# sensor_board_v0_52.net
KiCad netlist of a schematic drawn in EAGLE
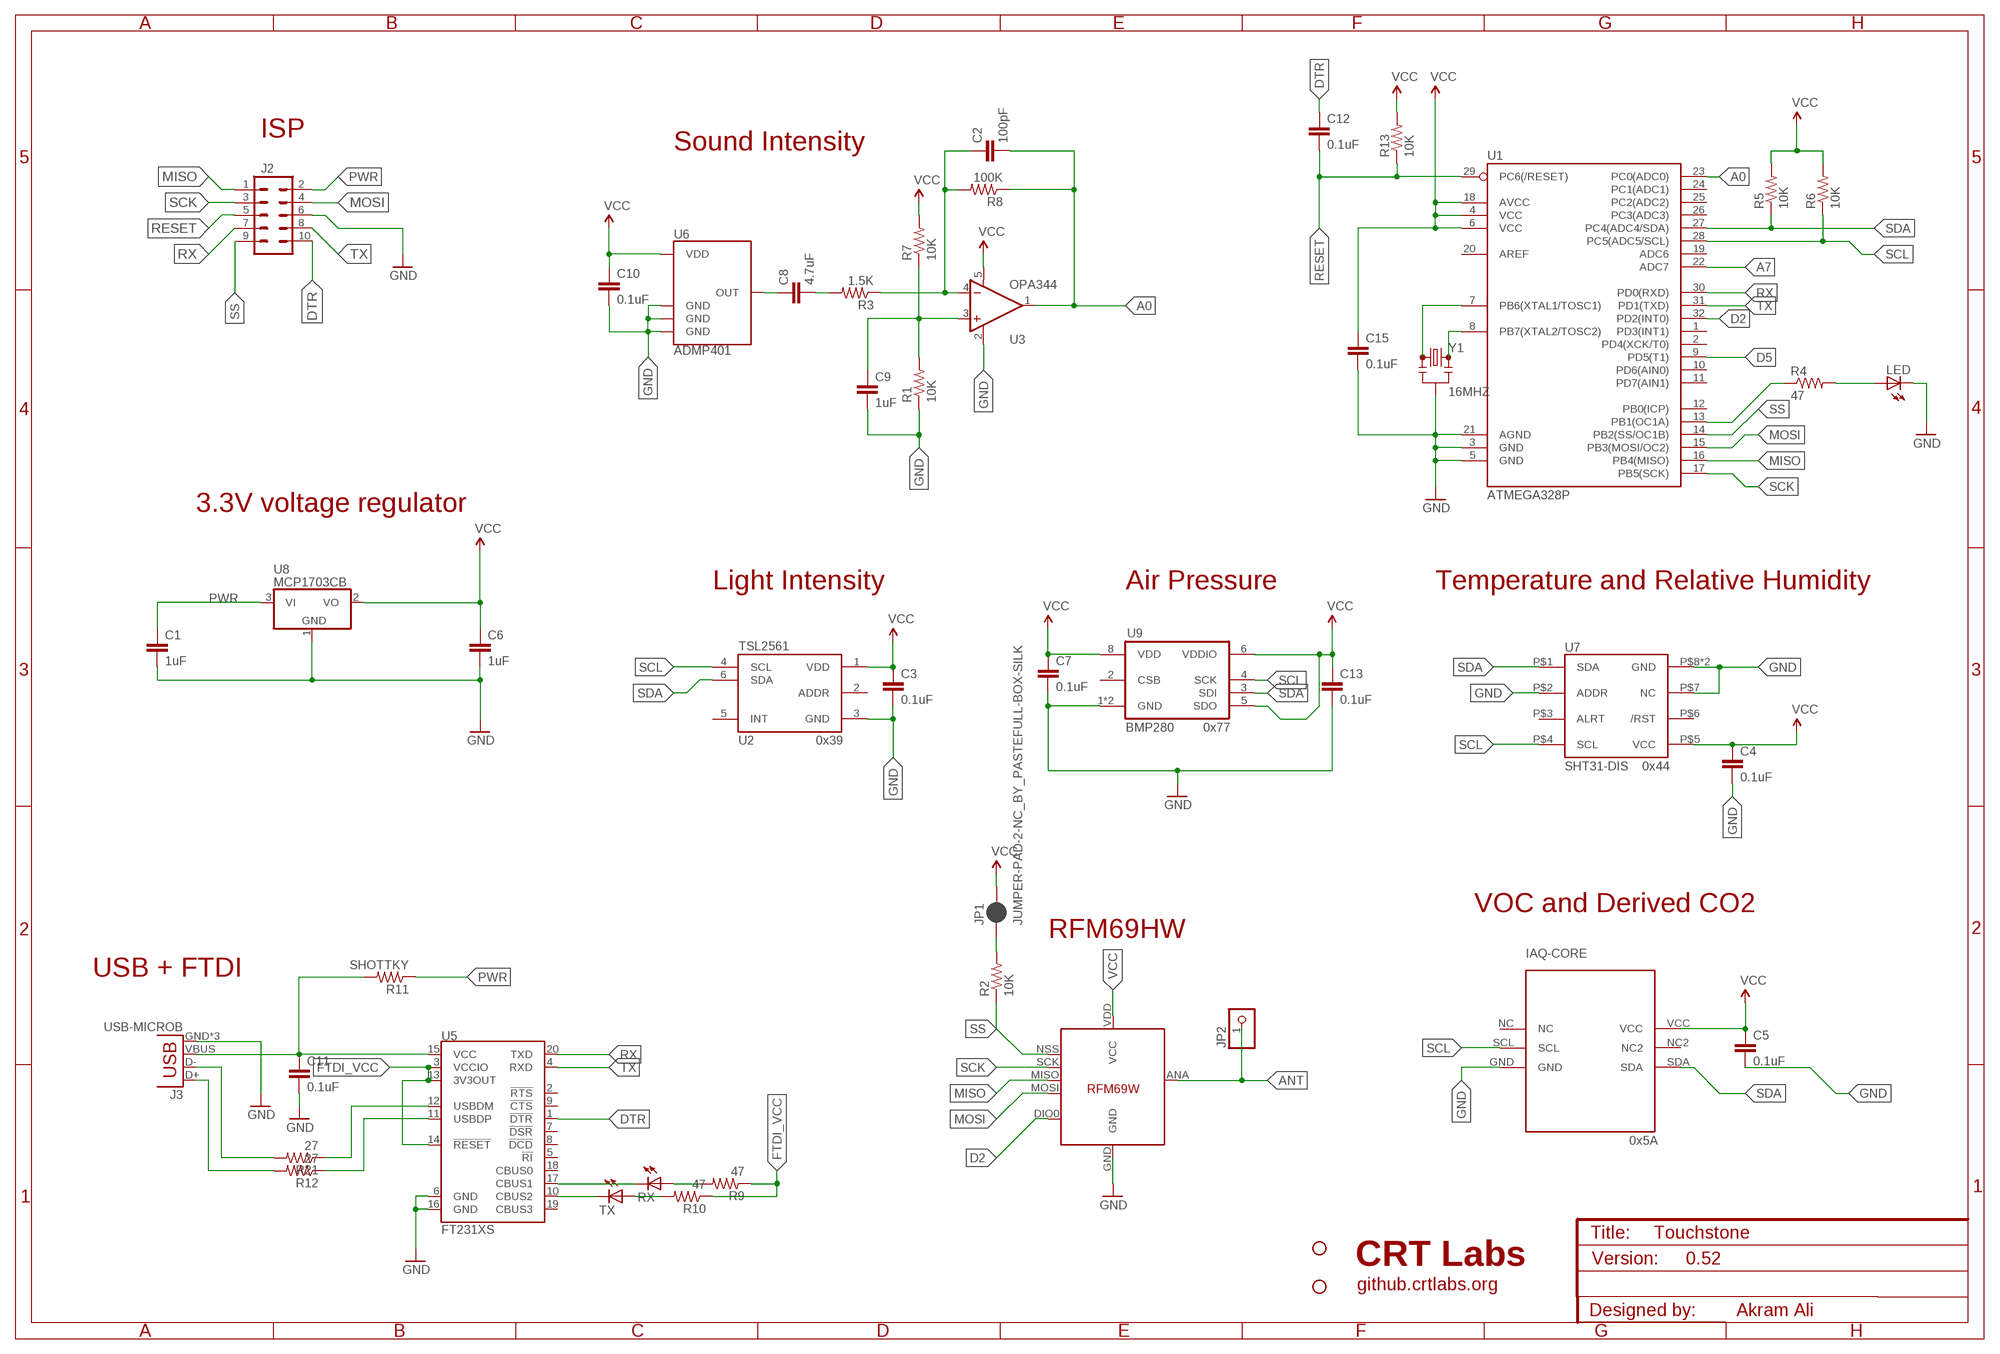
[diagram p0: schematic, sheet 1]

(export (version "E")
  (design (tool "Eeschema 10.0.6"))
  (components
    (comp (ref "C1")
      (value "1uF")
      (footprint "eagle-import:0805")
      (libsource (lib "eagle-import") (part "CAP0805"))
    )
    (comp (ref "C2")
      (value "100pF")
      (footprint "eagle-import:0805")
      (libsource (lib "eagle-import") (part "CAP0805"))
    )
    (comp (ref "C3")
      (value "0.1uF")
      (footprint "eagle-import:0805")
      (libsource (lib "eagle-import") (part "SparkFun-Passives_CAP0805"))
    )
    (comp (ref "C4")
      (value "0.1uF")
      (footprint "eagle-import:0805")
      (libsource (lib "eagle-import") (part "SparkFun-Passives_CAP0805"))
    )
    (comp (ref "C5")
      (value "0.1uF")
      (footprint "eagle-import:0805")
      (libsource (lib "eagle-import") (part "SparkFun-Passives_CAP0805"))
    )
    (comp (ref "C6")
      (value "1uF")
      (footprint "eagle-import:0805")
      (libsource (lib "eagle-import") (part "CAP0805"))
    )
    (comp (ref "C7")
      (value "0.1uF")
      (footprint "eagle-import:0805")
      (libsource (lib "eagle-import") (part "SparkFun-Passives_CAP0805"))
    )
    (comp (ref "C8")
      (value "4.7uF")
      (footprint "eagle-import:0805")
      (libsource (lib "eagle-import") (part "CAP0805"))
    )
    (comp (ref "C9")
      (value "1uF")
      (footprint "eagle-import:0805")
      (libsource (lib "eagle-import") (part "CAP0805"))
    )
    (comp (ref "C10")
      (value "0.1uF")
      (footprint "eagle-import:0805")
      (libsource (lib "eagle-import") (part "CAP0805"))
    )
    (comp (ref "C11")
      (value "0.1uF")
      (footprint "eagle-import:0805")
      (libsource (lib "eagle-import") (part "CAP0805"))
    )
    (comp (ref "C12")
      (value "0.1uF")
      (footprint "eagle-import:0805")
      (libsource (lib "eagle-import") (part "SparkFun-Passives_CAP0805"))
    )
    (comp (ref "C13")
      (value "0.1uF")
      (footprint "eagle-import:0805")
      (libsource (lib "eagle-import") (part "SparkFun-Passives_CAP0805"))
    )
    (comp (ref "C15")
      (value "0.1uF")
      (footprint "eagle-import:0805")
      (libsource (lib "eagle-import") (part "SparkFun-Passives_CAP0805"))
    )
    (comp (ref "H1")
      (value "STAND-OFF")
      (footprint "eagle-import:STAND-OFF")
      (libsource (lib "eagle-import") (part "STAND-OFF"))
    )
    (comp (ref "H2")
      (value "STAND-OFF")
      (footprint "eagle-import:STAND-OFF")
      (libsource (lib "eagle-import") (part "STAND-OFF"))
    )
    (comp (ref "IAQ-CORE")
      (value "IAQ-CORE")
      (footprint "eagle-import:IAQ-CORE")
      (fields (field (name "MPN") "IAQ CORE"))
      (libsource (lib "eagle-import") (part "IAQ-CORE"))
    )
    (comp (ref "J2")
      (value "M05X2PTH")
      (footprint "eagle-import:AVR_ICSP")
      (libsource (lib "eagle-import") (part "M05X2PTH"))
    )
    (comp (ref "J3")
      (value "USB-MICROB")
      (footprint "eagle-import:USB-MICROB")
      (libsource (lib "eagle-import") (part "USB-MICROB"))
    )
    (comp (ref "JP1")
      (value "JUMPER-PAD-2-NC_BY_PASTEFULL-BOX-SILK")
      (footprint "eagle-import:PAD-JUMPER-2-NC_BY_PASTE_YES_SILK_FULL_BOX")
      (libsource (lib "eagle-import") (part "JUMPER-PAD-2-NC_BY_PASTEFULL-BOX-SILK"))
    )
    (comp (ref "JP2")
      (value "PINHD-1X1")
      (footprint "eagle-import:1X01")
      (libsource (lib "eagle-import") (part "PINHD-1X1"))
    )
    (comp (ref "LED")
      (value "LEDCHIPLED_0805")
      (footprint "eagle-import:CHIPLED_0805")
      (libsource (lib "eagle-import") (part "LEDCHIPLED_0805"))
    )
    (comp (ref "R1")
      (value "10K")
      (footprint "eagle-import:0805")
      (libsource (lib "eagle-import") (part "RESISTOR0805-RES"))
    )
    (comp (ref "R2")
      (value "10K")
      (footprint "eagle-import:0805")
      (libsource (lib "eagle-import") (part "RESISTOR0805-RES"))
    )
    (comp (ref "R3")
      (value "1.5K")
      (footprint "eagle-import:0805")
      (libsource (lib "eagle-import") (part "RESISTOR0805-RES"))
    )
    (comp (ref "R4")
      (value "47")
      (footprint "eagle-import:0805")
      (libsource (lib "eagle-import") (part "SparkFun-Resistors_RESISTOR0805-RES"))
    )
    (comp (ref "R5")
      (value "10K")
      (footprint "eagle-import:0805")
      (libsource (lib "eagle-import") (part "SparkFun-Resistors_RESISTOR0805-RES"))
    )
    (comp (ref "R6")
      (value "10K")
      (footprint "eagle-import:0805")
      (libsource (lib "eagle-import") (part "SparkFun-Resistors_RESISTOR0805-RES"))
    )
    (comp (ref "R7")
      (value "10K")
      (footprint "eagle-import:0805")
      (libsource (lib "eagle-import") (part "RESISTOR0805-RES"))
    )
    (comp (ref "R8")
      (value "100K")
      (footprint "eagle-import:0805")
      (libsource (lib "eagle-import") (part "RESISTOR0805-RES"))
    )
    (comp (ref "R9")
      (value "47")
      (footprint "eagle-import:0805")
      (libsource (lib "eagle-import") (part "RESISTOR0805-RES"))
    )
    (comp (ref "R10")
      (value "47")
      (footprint "eagle-import:0805")
      (libsource (lib "eagle-import") (part "RESISTOR0805-RES"))
    )
    (comp (ref "R11")
      (value "SHOTTKY")
      (footprint "eagle-import:0805")
      (libsource (lib "eagle-import") (part "RESISTOR0805-RES"))
    )
    (comp (ref "R12")
      (value "27")
      (footprint "eagle-import:0805")
      (libsource (lib "eagle-import") (part "RESISTOR0805-RES"))
    )
    (comp (ref "R13")
      (value "10K")
      (footprint "eagle-import:0805")
      (libsource (lib "eagle-import") (part "RESISTOR0805-RES"))
    )
    (comp (ref "R21")
      (value "27")
      (footprint "eagle-import:0805")
      (libsource (lib "eagle-import") (part "RESISTOR0805-RES"))
    )
    (comp (ref "RX")
      (value "LEDCHIPLED_0805")
      (footprint "eagle-import:CHIPLED_0805")
      (libsource (lib "eagle-import") (part "LEDCHIPLED_0805"))
    )
    (comp (ref "TX")
      (value "LEDCHIPLED_0805")
      (footprint "eagle-import:CHIPLED_0805")
      (libsource (lib "eagle-import") (part "LEDCHIPLED_0805"))
    )
    (comp (ref "U1")
      (value "ATMEGA328P")
      (footprint "eagle-import:TQFP32-08")
      (fields (field (name "MPN") "ATMEGA328PB-AU"))
      (libsource (lib "eagle-import") (part "ATMEGA328P_TQFP"))
    )
    (comp (ref "U2")
      (value "TSL2561")
      (footprint "eagle-import:FN-6")
      (fields (field (name "MANF") "AMS-TAOS-USA-Inc.") (field (name "MPN") "TSL2561FN"))
      (libsource (lib "eagle-import") (part "TSL2561FN"))
    )
    (comp (ref "U3")
      (value "OPA344")
      (footprint "eagle-import:SOT23-5")
      (libsource (lib "eagle-import") (part "OPA344"))
    )
    (comp (ref "U4")
      (value "RFM69HW")
      (footprint "eagle-import:LOWPOWERLAB_RFM69W-MINPADS")
      (libsource (lib "eagle-import") (part "LOWPOWERLAB_RFM69"))
    )
    (comp (ref "U5")
      (value "FT231XS")
      (footprint "eagle-import:SSOP20_L")
      (libsource (lib "eagle-import") (part "FT231XS"))
    )
    (comp (ref "U6")
      (value "ADMP401")
      (footprint "eagle-import:ADMP401")
      (libsource (lib "eagle-import") (part "ADMP401"))
    )
    (comp (ref "U7")
      (value "SHT31-DIS")
      (footprint "eagle-import:SHT3X")
      (fields (field (name "MPN") "SHT31-DIS-B"))
      (libsource (lib "eagle-import") (part "SHT31-DIS"))
    )
    (comp (ref "U8")
      (value "MCP1703CB")
      (footprint "eagle-import:SOT23")
      (fields (field (name "MPN") "MCP1703T-2502E/CB"))
      (libsource (lib "eagle-import") (part "MCP1703CB"))
    )
    (comp (ref "U9")
      (value "BMP280")
      (footprint "eagle-import:BMP280")
      (libsource (lib "eagle-import") (part "BMP280"))
    )
    (comp (ref "Y1")
      (value "16MHZ")
      (footprint "eagle-import:RESONATOR-SMD")
      (libsource (lib "eagle-import") (part "RESONATOR16MHZ"))
    )
  )
  (nets
    (net (code "1") (name "A0") (class "Default")
      (node (ref "C2") (pin "2") (pinfunction "2_2") (pintype "passive"))
      (node (ref "R8") (pin "1") (pinfunction "1_1") (pintype "passive"))
      (node (ref "U1") (pin "23") (pinfunction "PC0(ADC0)_23") (pintype "bidirectional"))
      (node (ref "U3") (pin "1") (pinfunction "OUT_1") (pintype "output"))
    )
    (net (code "2") (name "A7") (class "Default")
      (node (ref "U1") (pin "22") (pinfunction "ADC7_22") (pintype "bidirectional"))
    )
    (net (code "3") (name "ANT") (class "Default")
      (node (ref "JP2") (pin "1") (pinfunction "1_1") (pintype "passive"))
      (node (ref "U4") (pin "ANA") (pinfunction "ANT_ANA") (pintype "passive"))
    )
    (net (code "4") (name "D2") (class "Default")
      (node (ref "U1") (pin "32") (pinfunction "PD2(INT0)_32") (pintype "bidirectional"))
      (node (ref "U4") (pin "DIO0") (pinfunction "DIO0_DIO0") (pintype "open_collector"))
    )
    (net (code "5") (name "D5") (class "Default")
      (node (ref "U1") (pin "9") (pinfunction "PD5(T1)_9") (pintype "bidirectional"))
    )
    (net (code "6") (name "DTR") (class "Default")
      (node (ref "C12") (pin "1") (pinfunction "1_1") (pintype "passive"))
      (node (ref "J2") (pin "10") (pinfunction "10_10") (pintype "passive"))
      (node (ref "U5") (pin "1") (pinfunction "~{DTR}_1") (pintype "bidirectional"))
    )
    (net (code "7") (name "FTDI_VCC") (class "Default")
      (node (ref "R10") (pin "1") (pinfunction "1_1") (pintype "passive"))
      (node (ref "R9") (pin "1") (pinfunction "1_1") (pintype "passive"))
      (node (ref "U5") (pin "13") (pinfunction "3V3OUT_13") (pintype "bidirectional"))
      (node (ref "U5") (pin "14") (pinfunction "~{RESET}_14") (pintype "bidirectional"))
      (node (ref "U5") (pin "3") (pinfunction "VCCIO_3") (pintype "bidirectional"))
    )
    (net (code "8") (name "GND") (class "Default")
      (node (ref "C1") (pin "2") (pinfunction "2_2") (pintype "passive"))
      (node (ref "C10") (pin "2") (pinfunction "2_2") (pintype "passive"))
      (node (ref "C11") (pin "2") (pinfunction "2_2") (pintype "passive"))
      (node (ref "C13") (pin "2") (pinfunction "2_2") (pintype "passive"))
      (node (ref "C15") (pin "2") (pinfunction "2_2") (pintype "passive"))
      (node (ref "C3") (pin "2") (pinfunction "2_2") (pintype "passive"))
      (node (ref "C4") (pin "2") (pinfunction "2_2") (pintype "passive"))
      (node (ref "C5") (pin "2") (pinfunction "2_2") (pintype "passive"))
      (node (ref "C6") (pin "2") (pinfunction "2_2") (pintype "passive"))
      (node (ref "C7") (pin "2") (pinfunction "2_2") (pintype "passive"))
      (node (ref "C9") (pin "2") (pinfunction "2_2") (pintype "passive"))
      (node (ref "IAQ-CORE") (pin "GND") (pinfunction "GND_GND") (pintype "bidirectional"))
      (node (ref "J2") (pin "6") (pinfunction "6_6") (pintype "passive"))
      (node (ref "J3") (pin "GND") (pinfunction "GND_GND") (pintype "bidirectional"))
      (node (ref "J3") (pin "MT1") (pinfunction "GND_MT1") (pintype "bidirectional"))
      (node (ref "J3") (pin "MT2") (pinfunction "GND_MT2") (pintype "bidirectional"))
      (node (ref "LED") (pin "C") (pinfunction "C_C") (pintype "passive"))
      (node (ref "R1") (pin "1") (pinfunction "1_1") (pintype "passive"))
      (node (ref "U1") (pin "21") (pinfunction "AGND_21") (pintype "bidirectional"))
      (node (ref "U1") (pin "3") (pinfunction "GND_3") (pintype "bidirectional"))
      (node (ref "U1") (pin "5") (pinfunction "GND_5") (pintype "bidirectional"))
      (node (ref "U2") (pin "3") (pinfunction "GND_3") (pintype "power_in"))
      (node (ref "U3") (pin "2") (pinfunction "V-_2") (pintype "power_in"))
      (node (ref "U4") (pin "GND") (pinfunction "GND_GND") (pintype "power_in"))
      (node (ref "U5") (pin "16") (pinfunction "GND_16") (pintype "bidirectional"))
      (node (ref "U5") (pin "6") (pinfunction "GND_6") (pintype "bidirectional"))
      (node (ref "U6") (pin "2") (pinfunction "GND_2") (pintype "bidirectional"))
      (node (ref "U6") (pin "4") (pinfunction "GND_4") (pintype "bidirectional"))
      (node (ref "U6") (pin "6") (pinfunction "GND_6") (pintype "bidirectional"))
      (node (ref "U7") (pin "P$2") (pinfunction "ADDR_P$2") (pintype "bidirectional"))
      (node (ref "U7") (pin "P$7") (pinfunction "NC_P$7") (pintype "bidirectional"))
      (node (ref "U7") (pin "P$8") (pinfunction "GND_P$8") (pintype "bidirectional"))
      (node (ref "U7") (pin "PAD") (pinfunction "GND_PAD") (pintype "bidirectional"))
      (node (ref "U8") (pin "1") (pinfunction "GND_1") (pintype "passive"))
      (node (ref "U9") (pin "1") (pinfunction "GND_1") (pintype "power_in"))
      (node (ref "U9") (pin "7") (pinfunction "GND_7") (pintype "power_in"))
      (node (ref "Y1") (pin "2") (pinfunction "2_2") (pintype "passive"))
    )
    (net (code "9") (name "MISO") (class "Default")
      (node (ref "J2") (pin "1") (pinfunction "1_1") (pintype "passive"))
      (node (ref "U1") (pin "16") (pinfunction "PB4(MISO)_16") (pintype "bidirectional"))
      (node (ref "U4") (pin "MISO") (pinfunction "MISO_MISO") (pintype "input"))
    )
    (net (code "10") (name "MOSI") (class "Default")
      (node (ref "J2") (pin "4") (pinfunction "4_4") (pintype "passive"))
      (node (ref "U1") (pin "15") (pinfunction "PB3(MOSI/OC2)_15") (pintype "bidirectional"))
      (node (ref "U4") (pin "MOSI") (pinfunction "MOSI_MOSI") (pintype "output"))
    )
    (net (code "11") (name "Net-(C8-Pad2)") (class "Default")
      (node (ref "C8") (pin "2") (pinfunction "2_2") (pintype "passive"))
      (node (ref "R3") (pin "2") (pinfunction "2_2") (pintype "passive"))
    )
    (net (code "12") (name "Net-(J3-PadD+)") (class "Default")
      (node (ref "J3") (pin "D+") (pinfunction "D+_D+") (pintype "bidirectional"))
      (node (ref "R12") (pin "2") (pinfunction "2_2") (pintype "passive"))
    )
    (net (code "13") (name "Net-(J3-PadD-)") (class "Default")
      (node (ref "J3") (pin "D-") (pinfunction "D-_D-") (pintype "bidirectional"))
      (node (ref "R21") (pin "2") (pinfunction "2_2") (pintype "passive"))
    )
    (net (code "14") (name "Net-(JP1-Pad1)") (class "Default")
      (node (ref "JP1") (pin "1") (pinfunction "1_1") (pintype "passive"))
      (node (ref "R2") (pin "2") (pinfunction "2_2") (pintype "passive"))
    )
    (net (code "15") (name "Net-(LED-PadA)") (class "Default")
      (node (ref "LED") (pin "A") (pinfunction "A_A") (pintype "passive"))
      (node (ref "R4") (pin "2") (pinfunction "2_2") (pintype "passive"))
    )
    (net (code "16") (name "Net-(R9-Pad2)") (class "Default")
      (node (ref "R9") (pin "2") (pinfunction "2_2") (pintype "passive"))
      (node (ref "RX") (pin "A") (pinfunction "A_A") (pintype "passive"))
    )
    (net (code "17") (name "Net-(R10-Pad2)") (class "Default")
      (node (ref "R10") (pin "2") (pinfunction "2_2") (pintype "passive"))
      (node (ref "TX") (pin "A") (pinfunction "A_A") (pintype "passive"))
    )
    (net (code "18") (name "Net-(U1-PB1(OC1A))") (class "Default")
      (node (ref "R4") (pin "1") (pinfunction "1_1") (pintype "passive"))
      (node (ref "U1") (pin "13") (pinfunction "PB1(OC1A)_13") (pintype "bidirectional"))
    )
    (net (code "19") (name "Net-(U1-PB6(XTAL1{slash}TOSC1))") (class "Default")
      (node (ref "U1") (pin "7") (pinfunction "PB6(XTAL1/TOSC1)_7") (pintype "bidirectional"))
      (node (ref "Y1") (pin "1") (pinfunction "1_1") (pintype "passive"))
    )
    (net (code "20") (name "Net-(U1-PB7(XTAL2{slash}TOSC2))") (class "Default")
      (node (ref "U1") (pin "8") (pinfunction "PB7(XTAL2/TOSC2)_8") (pintype "bidirectional"))
      (node (ref "Y1") (pin "3") (pinfunction "3_3") (pintype "passive"))
    )
    (net (code "21") (name "Net-(U3-+IN)") (class "Default")
      (node (ref "C9") (pin "1") (pinfunction "1_1") (pintype "passive"))
      (node (ref "R1") (pin "2") (pinfunction "2_2") (pintype "passive"))
      (node (ref "R7") (pin "1") (pinfunction "1_1") (pintype "passive"))
      (node (ref "U3") (pin "3") (pinfunction "+IN_3") (pintype "input"))
    )
    (net (code "22") (name "Net-(U3--IN)") (class "Default")
      (node (ref "C2") (pin "1") (pinfunction "1_1") (pintype "passive"))
      (node (ref "R3") (pin "1") (pinfunction "1_1") (pintype "passive"))
      (node (ref "R8") (pin "2") (pinfunction "2_2") (pintype "passive"))
      (node (ref "U3") (pin "4") (pinfunction "-IN_4") (pintype "input"))
    )
    (net (code "23") (name "Net-(U5-CBUS1)") (class "Default")
      (node (ref "RX") (pin "C") (pinfunction "C_C") (pintype "passive"))
      (node (ref "U5") (pin "17") (pinfunction "CBUS1_17") (pintype "bidirectional"))
    )
    (net (code "24") (name "Net-(U5-CBUS2)") (class "Default")
      (node (ref "TX") (pin "C") (pinfunction "C_C") (pintype "passive"))
      (node (ref "U5") (pin "10") (pinfunction "CBUS2_10") (pintype "bidirectional"))
    )
    (net (code "25") (name "Net-(U5-USBDM)") (class "Default")
      (node (ref "R21") (pin "1") (pinfunction "1_1") (pintype "passive"))
      (node (ref "U5") (pin "12") (pinfunction "USBDM_12") (pintype "bidirectional"))
    )
    (net (code "26") (name "Net-(U5-USBDP)") (class "Default")
      (node (ref "R12") (pin "1") (pinfunction "1_1") (pintype "passive"))
      (node (ref "U5") (pin "11") (pinfunction "USBDP_11") (pintype "bidirectional"))
    )
    (net (code "27") (name "Net-(U5-VCC)") (class "Default")
      (node (ref "C11") (pin "1") (pinfunction "1_1") (pintype "passive"))
      (node (ref "J3") (pin "VBUS") (pinfunction "VBUS_VBUS") (pintype "bidirectional"))
      (node (ref "R11") (pin "2") (pinfunction "2_2") (pintype "passive"))
      (node (ref "U5") (pin "15") (pinfunction "VCC_15") (pintype "bidirectional"))
    )
    (net (code "28") (name "Net-(U6-OUT)") (class "Default")
      (node (ref "C8") (pin "1") (pinfunction "1_1") (pintype "passive"))
      (node (ref "U6") (pin "1") (pinfunction "OUT_1") (pintype "bidirectional"))
    )
    (net (code "29") (name "PWR") (class "Default")
      (node (ref "C1") (pin "1") (pinfunction "1_1") (pintype "passive"))
      (node (ref "J2") (pin "2") (pinfunction "2_2") (pintype "passive"))
      (node (ref "R11") (pin "1") (pinfunction "1_1") (pintype "passive"))
      (node (ref "U8") (pin "3") (pinfunction "VI_3") (pintype "input"))
    )
    (net (code "30") (name "RESET") (class "Default")
      (node (ref "C12") (pin "2") (pinfunction "2_2") (pintype "passive"))
      (node (ref "J2") (pin "5") (pinfunction "5_5") (pintype "passive"))
      (node (ref "R13") (pin "1") (pinfunction "1_1") (pintype "passive"))
      (node (ref "U1") (pin "29") (pinfunction "PC6(/RESET)_29") (pintype "bidirectional"))
    )
    (net (code "31") (name "RX") (class "Default")
      (node (ref "J2") (pin "7") (pinfunction "7_7") (pintype "passive"))
      (node (ref "U1") (pin "30") (pinfunction "PD0(RXD)_30") (pintype "bidirectional"))
      (node (ref "U5") (pin "20") (pinfunction "TXD_20") (pintype "bidirectional"))
    )
    (net (code "32") (name "SCK") (class "Default")
      (node (ref "J2") (pin "3") (pinfunction "3_3") (pintype "passive"))
      (node (ref "U1") (pin "17") (pinfunction "PB5(SCK)_17") (pintype "bidirectional"))
      (node (ref "U4") (pin "SCK") (pinfunction "SCK_SCK") (pintype "input"))
    )
    (net (code "33") (name "SCL") (class "Default")
      (node (ref "IAQ-CORE") (pin "SCL") (pinfunction "SCL_SCL") (pintype "bidirectional"))
      (node (ref "R6") (pin "1") (pinfunction "1_1") (pintype "passive"))
      (node (ref "U1") (pin "28") (pinfunction "PC5(ADC5/SCL)_28") (pintype "bidirectional"))
      (node (ref "U2") (pin "4") (pinfunction "SCL_4") (pintype "input"))
      (node (ref "U7") (pin "P$4") (pinfunction "SCL_P$4") (pintype "bidirectional"))
      (node (ref "U9") (pin "4") (pinfunction "SCK_4") (pintype "bidirectional"))
    )
    (net (code "34") (name "SDA") (class "Default")
      (node (ref "IAQ-CORE") (pin "SDA") (pinfunction "SDA_SDA") (pintype "bidirectional"))
      (node (ref "R5") (pin "1") (pinfunction "1_1") (pintype "passive"))
      (node (ref "U1") (pin "27") (pinfunction "PC4(ADC4/SDA)_27") (pintype "bidirectional"))
      (node (ref "U2") (pin "6") (pinfunction "SDA_6") (pintype "bidirectional"))
      (node (ref "U7") (pin "P$1") (pinfunction "SDA_P$1") (pintype "bidirectional"))
      (node (ref "U9") (pin "3") (pinfunction "SDI_3") (pintype "bidirectional"))
    )
    (net (code "35") (name "SS") (class "Default")
      (node (ref "J2") (pin "9") (pinfunction "9_9") (pintype "passive"))
      (node (ref "R2") (pin "1") (pinfunction "1_1") (pintype "passive"))
      (node (ref "U1") (pin "14") (pinfunction "PB2(SS/OC1B)_14") (pintype "bidirectional"))
      (node (ref "U4") (pin "NSS") (pinfunction "SEL_NSS") (pintype "input"))
    )
    (net (code "36") (name "TX") (class "Default")
      (node (ref "J2") (pin "8") (pinfunction "8_8") (pintype "passive"))
      (node (ref "U1") (pin "31") (pinfunction "PD1(TXD)_31") (pintype "bidirectional"))
      (node (ref "U5") (pin "4") (pinfunction "RXD_4") (pintype "bidirectional"))
    )
    (net (code "37") (name "VCC") (class "Default")
      (node (ref "C10") (pin "1") (pinfunction "1_1") (pintype "passive"))
      (node (ref "C13") (pin "1") (pinfunction "1_1") (pintype "passive"))
      (node (ref "C15") (pin "1") (pinfunction "1_1") (pintype "passive"))
      (node (ref "C3") (pin "1") (pinfunction "1_1") (pintype "passive"))
      (node (ref "C4") (pin "1") (pinfunction "1_1") (pintype "passive"))
      (node (ref "C5") (pin "1") (pinfunction "1_1") (pintype "passive"))
      (node (ref "C6") (pin "1") (pinfunction "1_1") (pintype "passive"))
      (node (ref "C7") (pin "1") (pinfunction "1_1") (pintype "passive"))
      (node (ref "IAQ-CORE") (pin "VCC") (pinfunction "VCC_VCC") (pintype "bidirectional"))
      (node (ref "JP1") (pin "2") (pinfunction "2_2") (pintype "passive"))
      (node (ref "R13") (pin "2") (pinfunction "2_2") (pintype "passive"))
      (node (ref "R5") (pin "2") (pinfunction "2_2") (pintype "passive"))
      (node (ref "R6") (pin "2") (pinfunction "2_2") (pintype "passive"))
      (node (ref "R7") (pin "2") (pinfunction "2_2") (pintype "passive"))
      (node (ref "U1") (pin "18") (pinfunction "AVCC_18") (pintype "bidirectional"))
      (node (ref "U1") (pin "4") (pinfunction "VCC_4") (pintype "bidirectional"))
      (node (ref "U1") (pin "6") (pinfunction "VCC_6") (pintype "bidirectional"))
      (node (ref "U2") (pin "1") (pinfunction "VDD_1") (pintype "power_in"))
      (node (ref "U3") (pin "5") (pinfunction "V+_5") (pintype "power_in"))
      (node (ref "U4") (pin "VDD") (pinfunction "VCC_VDD") (pintype "power_in"))
      (node (ref "U6") (pin "5") (pinfunction "VDD_5") (pintype "bidirectional"))
      (node (ref "U7") (pin "P$5") (pinfunction "VCC_P$5") (pintype "bidirectional"))
      (node (ref "U8") (pin "2") (pinfunction "VO_2") (pintype "passive"))
      (node (ref "U9") (pin "5") (pinfunction "SDO_5") (pintype "input"))
      (node (ref "U9") (pin "6") (pinfunction "VDDIO_6") (pintype "power_in"))
      (node (ref "U9") (pin "8") (pinfunction "VDD_8") (pintype "power_in"))
    )
    (net (code "38") (name "unconnected-(IAQ-CORE-PadNC)") (class "Default")
      (node (ref "IAQ-CORE") (pin "NC") (pinfunction "NC_NC") (pintype "bidirectional"))
    )
    (net (code "39") (name "unconnected-(IAQ-CORE-PadNC2)") (class "Default")
      (node (ref "IAQ-CORE") (pin "NC2") (pinfunction "NC2_NC2") (pintype "bidirectional"))
    )
    (net (code "40") (name "unconnected-(U1-ADC6-Pad19)") (class "Default")
      (node (ref "U1") (pin "19") (pinfunction "ADC6_19") (pintype "bidirectional"))
    )
    (net (code "41") (name "unconnected-(U1-AREF-Pad20)") (class "Default")
      (node (ref "U1") (pin "20") (pinfunction "AREF_20") (pintype "bidirectional"))
    )
    (net (code "42") (name "unconnected-(U1-PB0(ICP)-Pad12)") (class "Default")
      (node (ref "U1") (pin "12") (pinfunction "PB0(ICP)_12") (pintype "bidirectional"))
    )
    (net (code "43") (name "unconnected-(U1-PC1(ADC1)-Pad24)") (class "Default")
      (node (ref "U1") (pin "24") (pinfunction "PC1(ADC1)_24") (pintype "bidirectional"))
    )
    (net (code "44") (name "unconnected-(U1-PC2(ADC2)-Pad25)") (class "Default")
      (node (ref "U1") (pin "25") (pinfunction "PC2(ADC2)_25") (pintype "bidirectional"))
    )
    (net (code "45") (name "unconnected-(U1-PC3(ADC3)-Pad26)") (class "Default")
      (node (ref "U1") (pin "26") (pinfunction "PC3(ADC3)_26") (pintype "bidirectional"))
    )
    (net (code "46") (name "unconnected-(U1-PD3(INT1)-Pad1)") (class "Default")
      (node (ref "U1") (pin "1") (pinfunction "PD3(INT1)_1") (pintype "bidirectional"))
    )
    (net (code "47") (name "unconnected-(U1-PD4(XCK{slash}T0)-Pad2)") (class "Default")
      (node (ref "U1") (pin "2") (pinfunction "PD4(XCK/T0)_2") (pintype "bidirectional"))
    )
    (net (code "48") (name "unconnected-(U1-PD6(AIN0)-Pad10)") (class "Default")
      (node (ref "U1") (pin "10") (pinfunction "PD6(AIN0)_10") (pintype "bidirectional"))
    )
    (net (code "49") (name "unconnected-(U1-PD7(AIN1)-Pad11)") (class "Default")
      (node (ref "U1") (pin "11") (pinfunction "PD7(AIN1)_11") (pintype "bidirectional"))
    )
    (net (code "50") (name "unconnected-(U2-ADDR-Pad2)") (class "Default")
      (node (ref "U2") (pin "2") (pinfunction "ADDR_2") (pintype "input"))
    )
    (net (code "51") (name "unconnected-(U2-INT-Pad5)") (class "Default")
      (node (ref "U2") (pin "5") (pinfunction "INT_5") (pintype "output"))
    )
    (net (code "52") (name "unconnected-(U5-CBUS0-Pad18)") (class "Default")
      (node (ref "U5") (pin "18") (pinfunction "CBUS0_18") (pintype "bidirectional"))
    )
    (net (code "53") (name "unconnected-(U5-CBUS3-Pad19)") (class "Default")
      (node (ref "U5") (pin "19") (pinfunction "CBUS3_19") (pintype "bidirectional"))
    )
    (net (code "54") (name "unconnected-(U5-~{CTS}-Pad9)") (class "Default")
      (node (ref "U5") (pin "9") (pinfunction "~{CTS}_9") (pintype "bidirectional"))
    )
    (net (code "55") (name "unconnected-(U5-~{DCD}-Pad8)") (class "Default")
      (node (ref "U5") (pin "8") (pinfunction "~{DCD}_8") (pintype "bidirectional"))
    )
    (net (code "56") (name "unconnected-(U5-~{DSR}-Pad7)") (class "Default")
      (node (ref "U5") (pin "7") (pinfunction "~{DSR}_7") (pintype "bidirectional"))
    )
    (net (code "57") (name "unconnected-(U5-~{RI}-Pad5)") (class "Default")
      (node (ref "U5") (pin "5") (pinfunction "~{RI}_5") (pintype "bidirectional"))
    )
    (net (code "58") (name "unconnected-(U5-~{RTS}-Pad2)") (class "Default")
      (node (ref "U5") (pin "2") (pinfunction "~{RTS}_2") (pintype "bidirectional"))
    )
    (net (code "59") (name "unconnected-(U7-ALRT-PadP$3)") (class "Default")
      (node (ref "U7") (pin "P$3") (pinfunction "ALRT_P$3") (pintype "bidirectional"))
    )
    (net (code "60") (name "unconnected-(U7-{slash}RST-PadP$6)") (class "Default")
      (node (ref "U7") (pin "P$6") (pinfunction "/RST_P$6") (pintype "bidirectional"))
    )
    (net (code "61") (name "unconnected-(U9-CSB-Pad2)") (class "Default")
      (node (ref "U9") (pin "2") (pinfunction "CSB_2") (pintype "input"))
    )
  )
)
